# EEPROM_Temp.net
KiCad netlist of a schematic drawn in Altium Designer
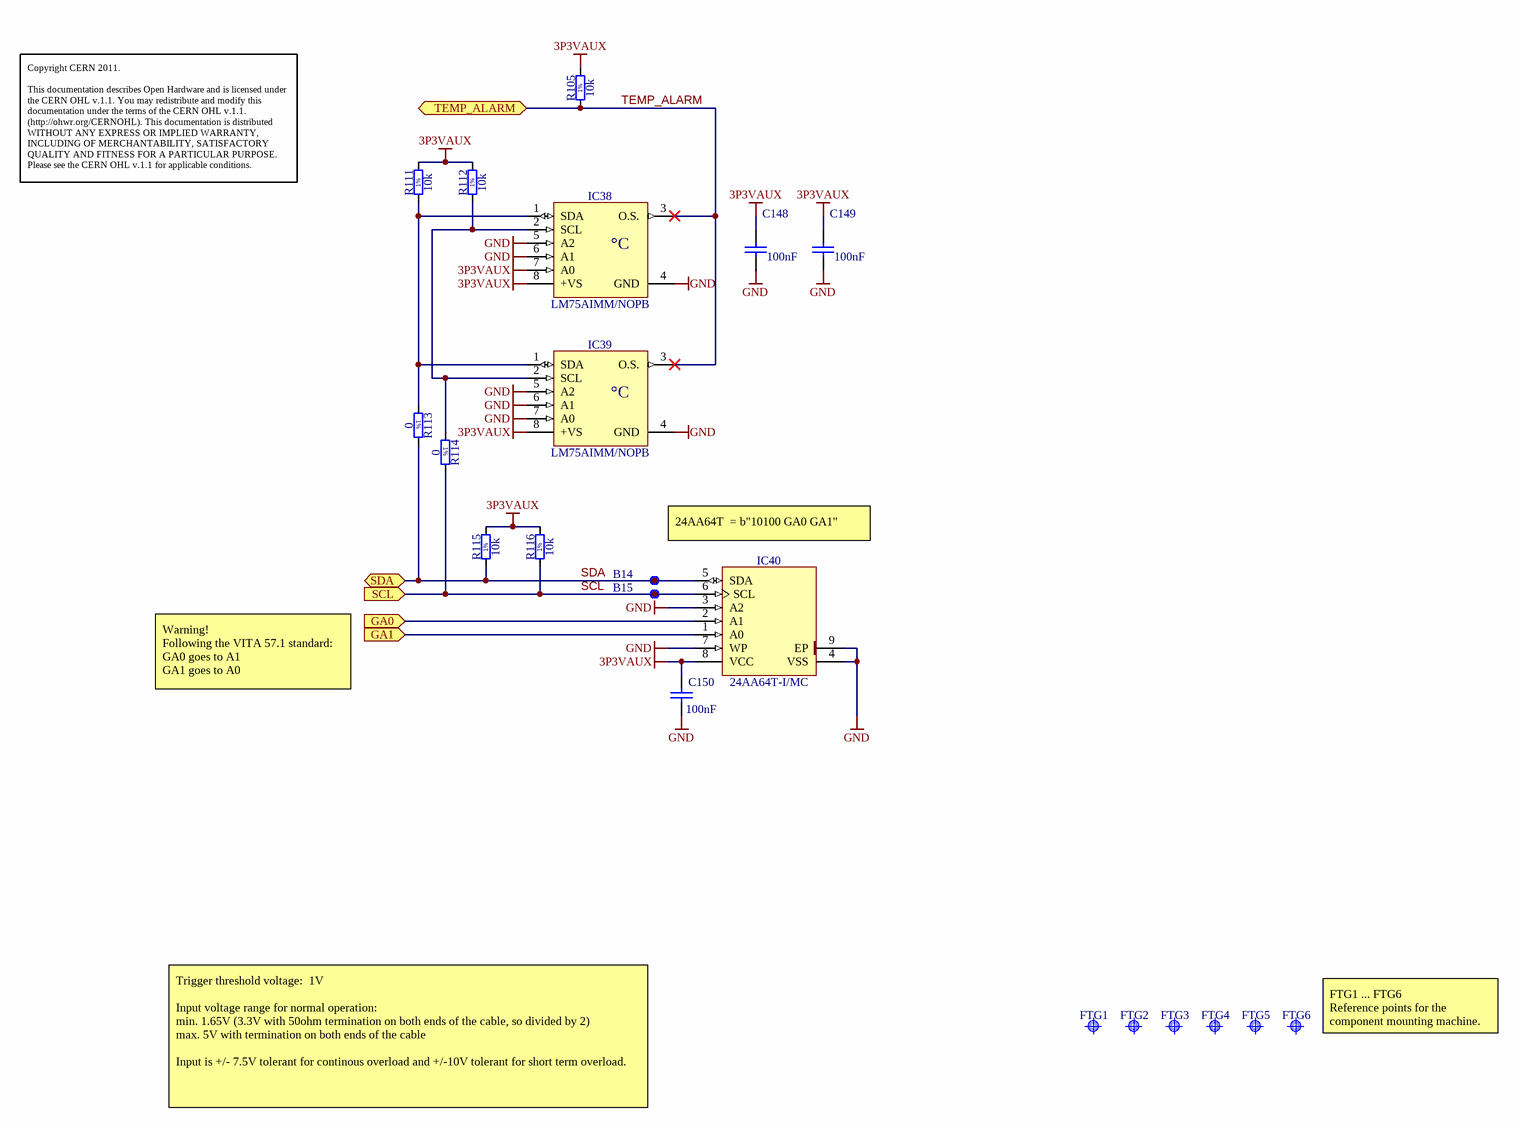
[diagram p0: EEPROM_Temp.SchDoc]

(export (version "E")
  (design (tool "Eeschema 10.0.6"))
  (components
    (comp (ref "B14")
      (value "SMD Pad")
      (footprint "C100")
      (description "Through Hole Pad")
      (fields (field (name "PART NUMBER") "SMD_PAD_D1MM") (field (name "AUTHOR") "CERN DEM JLC"))
      (libsource (lib "Eletro-mechanical") (part "Single SMD Pad (Round)"))
    )
    (comp (ref "B15")
      (value "SMD Pad")
      (footprint "C100")
      (description "Through Hole Pad")
      (fields (field (name "PART NUMBER") "SMD_PAD_D1MM") (field (name "AUTHOR") "CERN DEM JLC"))
      (libsource (lib "Eletro-mechanical") (part "Single SMD Pad (Round)"))
    )
    (comp (ref "C148")
      (value "100nF")
      (footprint "CAPC0603X33N")
      (description "Non-polarised capacitor")
      (fields
        (field (name "PART NUMBER") "CC0201_100NF_6.3V_10%_X5R")
        (field (name "VOLTAGE") "6.3V")
        (field (name "AUTHOR") "CERN DEM JLC")
      )
      (libsource (lib "Capacitors") (part "Capacitor - non polarized"))
    )
    (comp (ref "C149")
      (value "100nF")
      (footprint "CAPC0603X33N")
      (description "Non-polarised capacitor")
      (fields
        (field (name "PART NUMBER") "CC0201_100NF_6.3V_10%_X5R")
        (field (name "VOLTAGE") "6.3V")
        (field (name "AUTHOR") "CERN DEM JLC")
      )
      (libsource (lib "Capacitors") (part "Capacitor - non polarized"))
    )
    (comp (ref "C150")
      (value "100nF")
      (footprint "CAPC0603X33N")
      (description "Non-polarised capacitor")
      (fields
        (field (name "PART NUMBER") "CC0201_100NF_6.3V_10%_X5R")
        (field (name "VOLTAGE") "6.3V")
        (field (name "AUTHOR") "CERN DEM JLC")
      )
      (libsource (lib "Capacitors") (part "Capacitor - non polarized"))
    )
    (comp (ref "FTG1")
      (value "Use only in PCB")
      (footprint "FIDUCIAL_TOP_S100-200")
      (description "Fiducial Target")
      (fields (field (name "PART NUMBER") "FIDUCIAL_TARGET_S100-200") (field (name "AUTHOR") "CERN DEM JLC"))
      (libsource (lib "Eletro-mechanical") (part "Fiducial Target"))
    )
    (comp (ref "FTG2")
      (value "Use only in PCB")
      (footprint "FIDUCIAL_TOP_S100-200")
      (description "Fiducial Target")
      (fields (field (name "PART NUMBER") "FIDUCIAL_TARGET_S100-200") (field (name "AUTHOR") "CERN DEM JLC"))
      (libsource (lib "Eletro-mechanical") (part "Fiducial Target"))
    )
    (comp (ref "FTG3")
      (value "Use only in PCB")
      (footprint "FIDUCIAL_TOP_S100-200")
      (description "Fiducial Target")
      (fields (field (name "PART NUMBER") "FIDUCIAL_TARGET_S100-200") (field (name "AUTHOR") "CERN DEM JLC"))
      (libsource (lib "Eletro-mechanical") (part "Fiducial Target"))
    )
    (comp (ref "FTG4")
      (value "Use only in PCB")
      (footprint "FIDUCIAL_TOP_S100-200")
      (description "Fiducial Target")
      (fields (field (name "PART NUMBER") "FIDUCIAL_TARGET_S100-200") (field (name "AUTHOR") "CERN DEM JLC"))
      (libsource (lib "Eletro-mechanical") (part "Fiducial Target"))
    )
    (comp (ref "FTG5")
      (value "Use only in PCB")
      (footprint "FIDUCIAL_TOP_S100-200")
      (description "Fiducial Target")
      (fields (field (name "PART NUMBER") "FIDUCIAL_TARGET_S100-200") (field (name "AUTHOR") "CERN DEM JLC"))
      (libsource (lib "Eletro-mechanical") (part "Fiducial Target"))
    )
    (comp (ref "FTG6")
      (value "Use only in PCB")
      (footprint "FIDUCIAL_TOP_S100-200")
      (description "Fiducial Target")
      (fields (field (name "PART NUMBER") "FIDUCIAL_TARGET_S100-200") (field (name "AUTHOR") "CERN DEM JLC"))
      (libsource (lib "Eletro-mechanical") (part "Fiducial Target"))
    )
    (comp (ref "IC38")
      (value "LM75AIMM/NOPB")
      (footprint "SOP65P490X109-8N")
      (description "Digital Temperature Sensor and Thermal Watchdog with Two-Wire Interface")
      (fields (field (name "MANUFACTURER") "TEXAS INSTRUMENTS") (field (name "AUTHOR") "CERN DEM JLC"))
      (libsource (lib "ICs And Semiconductors") (part "LM75"))
    )
    (comp (ref "IC39")
      (value "LM75AIMM/NOPB")
      (footprint "SOP65P490X109-8N")
      (description "Digital Temperature Sensor and Thermal Watchdog with Two-Wire Interface")
      (fields (field (name "MANUFACTURER") "TEXAS INSTRUMENTS") (field (name "AUTHOR") "CERN DEM JLC"))
      (libsource (lib "ICs And Semiconductors") (part "LM75"))
    )
    (comp (ref "IC40")
      (value "24AA64T-I/MC")
      (footprint "SON50P300X200X100-9N-S175X155")
      (description "1.7-5.5V 64K I2C Serial EEPROM")
      (fields (field (name "MANUFACTURER") "MICROCHIP TECHNOLOGY") (field (name "AUTHOR") "CERN DEM JLC"))
      (libsource (lib "ICs And Semiconductors") (part "24AA64T-I/MC"))
    )
    (comp (ref "R105")
      (value "10k")
      (footprint "RESC1005X40N")
      (description "Resistor - 1%")
      (fields
        (field (name "PART NUMBER") "R0402_10K_1%_0.0625W_100PPM")
        (field (name "POWER") "0.0625W")
        (field (name "AUTHOR") "CERN DEM JLC")
      )
      (libsource (lib "Resistors") (part "Resistor - 1%"))
    )
    (comp (ref "R111")
      (value "10k")
      (footprint "RESC1005X40N")
      (description "Resistor - 1%")
      (fields
        (field (name "PART NUMBER") "R0402_10K_1%_0.0625W_100PPM")
        (field (name "POWER") "0.0625W")
        (field (name "AUTHOR") "CERN DEM JLC")
      )
      (libsource (lib "Resistors") (part "Resistor - 1%"))
    )
    (comp (ref "R112")
      (value "10k")
      (footprint "RESC1005X40N")
      (description "Resistor - 1%")
      (fields
        (field (name "PART NUMBER") "R0402_10K_1%_0.0625W_100PPM")
        (field (name "POWER") "0.0625W")
        (field (name "AUTHOR") "CERN DEM JLC")
      )
      (libsource (lib "Resistors") (part "Resistor - 1%"))
    )
    (comp (ref "R113")
      (value "0")
      (footprint "RESC1005X40N")
      (description "Resistor - 1%")
      (fields
        (field (name "PART NUMBER") "R0402_0R_JUMPER")
        (field (name "MANUFACTURER") "GENERIC")
        (field (name "AUTHOR") "CERN DEM JLC")
      )
      (libsource (lib "Resistors") (part "Resistor - 1%"))
    )
    (comp (ref "R114")
      (value "0")
      (footprint "RESC1005X40N")
      (description "Resistor - 1%")
      (fields
        (field (name "PART NUMBER") "R0402_0R_JUMPER")
        (field (name "MANUFACTURER") "GENERIC")
        (field (name "AUTHOR") "CERN DEM JLC")
      )
      (libsource (lib "Resistors") (part "Resistor - 1%"))
    )
    (comp (ref "R115")
      (value "10k")
      (footprint "RESC1005X40N")
      (description "Resistor - 1%")
      (fields
        (field (name "PART NUMBER") "R0402_10K_1%_0.0625W_100PPM")
        (field (name "POWER") "0.0625W")
        (field (name "AUTHOR") "CERN DEM JLC")
      )
      (libsource (lib "Resistors") (part "Resistor - 1%"))
    )
    (comp (ref "R116")
      (value "10k")
      (footprint "RESC1005X40N")
      (description "Resistor - 1%")
      (fields
        (field (name "PART NUMBER") "R0402_10K_1%_0.0625W_100PPM")
        (field (name "POWER") "0.0625W")
        (field (name "AUTHOR") "CERN DEM JLC")
      )
      (libsource (lib "Resistors") (part "Resistor - 1%"))
    )
  )
  (nets
    (net (code "1") (name "/GA0") (class "Default")
      (node (ref "IC40") (pin "2") (pinfunction "A1_2") (pintype "input"))
    )
    (net (code "2") (name "/GA1") (class "Default")
      (node (ref "IC40") (pin "1") (pinfunction "A0_1") (pintype "input"))
    )
    (net (code "3") (name "/SCL") (class "Default")
      (node (ref "B15") (pin "1") (pinfunction "1_1") (pintype "bidirectional"))
      (node (ref "IC40") (pin "6") (pinfunction "SCL_6") (pintype "input"))
      (node (ref "R114") (pin "2") (pinfunction "2_2") (pintype "passive"))
      (node (ref "R116") (pin "1") (pinfunction "1_1") (pintype "passive"))
    )
    (net (code "4") (name "/SDA") (class "Default")
      (node (ref "B14") (pin "1") (pinfunction "1_1") (pintype "bidirectional"))
      (node (ref "IC40") (pin "5") (pinfunction "SDA_5") (pintype "bidirectional"))
      (node (ref "R113") (pin "2") (pinfunction "2_2") (pintype "passive"))
      (node (ref "R115") (pin "1") (pinfunction "1_1") (pintype "passive"))
    )
    (net (code "5") (name "/TEMP_ALARM") (class "Default")
      (node (ref "IC38") (pin "3") (pinfunction "O.S._3") (pintype "output"))
      (node (ref "IC39") (pin "3") (pinfunction "O.S._3") (pintype "output"))
      (node (ref "R105") (pin "1") (pinfunction "1_1") (pintype "passive"))
    )
    (net (code "6") (name "3P3VAUX") (class "Default")
      (node (ref "C148") (pin "1") (pinfunction "1_1") (pintype "passive"))
      (node (ref "C149") (pin "1") (pinfunction "1_1") (pintype "passive"))
      (node (ref "C150") (pin "1") (pinfunction "1_1") (pintype "passive"))
      (node (ref "IC38") (pin "7") (pinfunction "A0_7") (pintype "input"))
      (node (ref "IC38") (pin "8") (pinfunction "+VS_8") (pintype "power_in"))
      (node (ref "IC39") (pin "8") (pinfunction "+VS_8") (pintype "power_in"))
      (node (ref "IC40") (pin "8") (pinfunction "VCC_8") (pintype "power_in"))
      (node (ref "R105") (pin "2") (pinfunction "2_2") (pintype "passive"))
      (node (ref "R111") (pin "2") (pinfunction "2_2") (pintype "passive"))
      (node (ref "R112") (pin "2") (pinfunction "2_2") (pintype "passive"))
      (node (ref "R115") (pin "2") (pinfunction "2_2") (pintype "passive"))
      (node (ref "R116") (pin "2") (pinfunction "2_2") (pintype "passive"))
    )
    (net (code "7") (name "GND") (class "Default")
      (node (ref "C148") (pin "2") (pinfunction "2_2") (pintype "passive"))
      (node (ref "C149") (pin "2") (pinfunction "2_2") (pintype "passive"))
      (node (ref "C150") (pin "2") (pinfunction "2_2") (pintype "passive"))
      (node (ref "IC38") (pin "4") (pinfunction "GND_4") (pintype "power_in"))
      (node (ref "IC38") (pin "5") (pinfunction "A2_5") (pintype "input"))
      (node (ref "IC38") (pin "6") (pinfunction "A1_6") (pintype "input"))
      (node (ref "IC39") (pin "4") (pinfunction "GND_4") (pintype "power_in"))
      (node (ref "IC39") (pin "5") (pinfunction "A2_5") (pintype "input"))
      (node (ref "IC39") (pin "6") (pinfunction "A1_6") (pintype "input"))
      (node (ref "IC39") (pin "7") (pinfunction "A0_7") (pintype "input"))
      (node (ref "IC40") (pin "3") (pinfunction "A2_3") (pintype "input"))
      (node (ref "IC40") (pin "4") (pinfunction "VSS_4") (pintype "power_in"))
      (node (ref "IC40") (pin "7") (pinfunction "WP_7") (pintype "input"))
      (node (ref "IC40") (pin "9") (pinfunction "EP_9") (pintype "power_in"))
    )
    (net (code "8") (name "Net-(IC38-SCL)") (class "Default")
      (node (ref "IC38") (pin "2") (pinfunction "SCL_2") (pintype "input"))
      (node (ref "IC39") (pin "2") (pinfunction "SCL_2") (pintype "input"))
      (node (ref "R112") (pin "1") (pinfunction "1_1") (pintype "passive"))
      (node (ref "R114") (pin "1") (pinfunction "1_1") (pintype "passive"))
    )
    (net (code "9") (name "Net-(IC38-SDA)") (class "Default")
      (node (ref "IC38") (pin "1") (pinfunction "SDA_1") (pintype "bidirectional"))
      (node (ref "IC39") (pin "1") (pinfunction "SDA_1") (pintype "bidirectional"))
      (node (ref "R111") (pin "1") (pinfunction "1_1") (pintype "passive"))
      (node (ref "R113") (pin "1") (pinfunction "1_1") (pintype "passive"))
    )
  )
)
